# schematic.net
KiCad netlist of a schematic drawn in EasyEDA
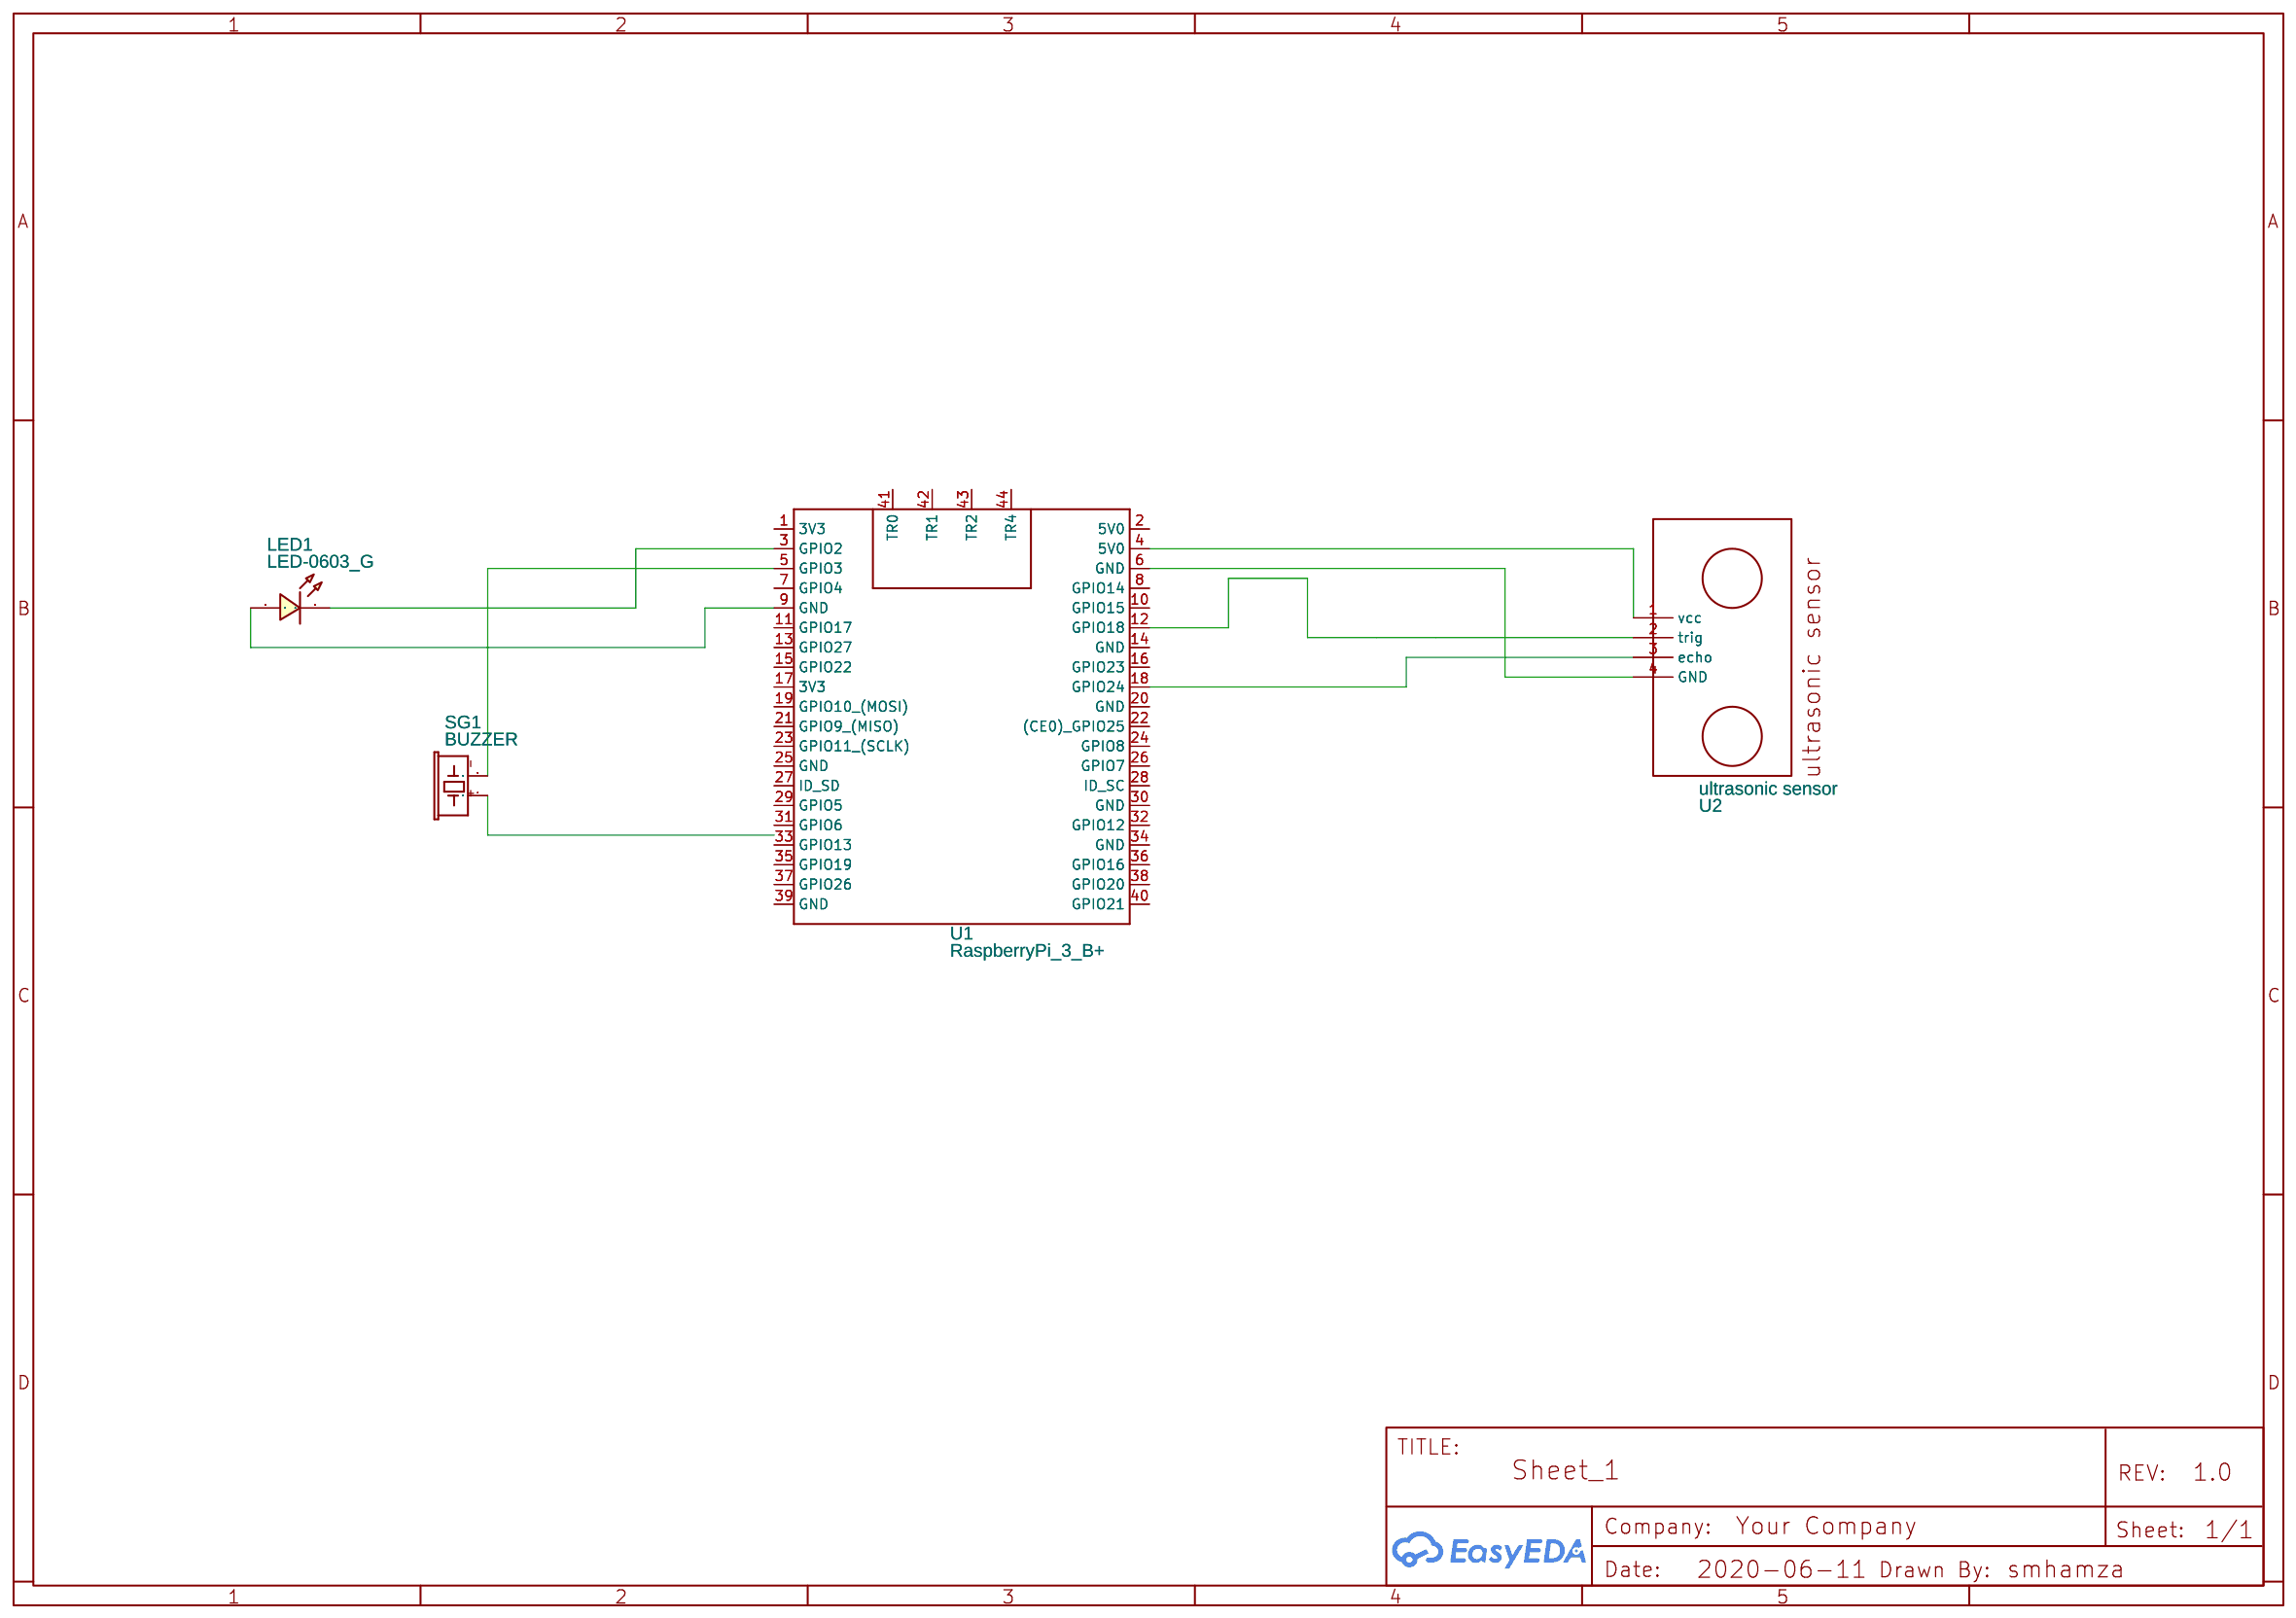
[diagram p0: schematic sheet]

(export (version "E")
  (design (tool "Eeschema 10.0.6"))
  (components
    (comp (ref "LED1")
      (value "LED-0603_G")
      (fields
        (field (name "BOM_Manufacturer Part") "19-217/GHC-YR1S2/3T")
        (field (name "BOM_Supplier Part") "C72043")
      )
      (libsource (lib "") (part "LED-0603_G"))
    )
    (comp (ref "SG1") (value "BUZZER") (libsource (lib "") (part "BUZZER")))
    (comp (ref "U1")
      (value "RaspberryPi_3_B+")
      (fields (field (name "BOM_Manufacturer Part") "RaspberryPi 3"))
      (libsource (lib "") (part "RaspberryPi_3_B+"))
    )
    (comp (ref "U2") (value "ultrasonic sensor") (libsource (lib "") (part "ultrasonic sensor")))
  )
  (nets
    (net (code "1") (name "Net-(LED1-Pad1)") (class "Default")
      (node (ref "LED1") (pin "1") (pinfunction "1_1") (pintype "unspecified"))
      (node (ref "U1") (pin "9") (pinfunction "GND_9") (pintype "unspecified"))
    )
    (net (code "2") (name "Net-(U1-GPIO2)") (class "Default")
      (node (ref "LED1") (pin "2") (pinfunction "2_2") (pintype "unspecified"))
      (node (ref "U1") (pin "3") (pinfunction "GPIO2_3") (pintype "unspecified"))
    )
    (net (code "3") (name "Net-(U1-GPIO3)") (class "Default")
      (node (ref "SG1") (pin "2") (pinfunction "2_2") (pintype "unspecified"))
      (node (ref "U1") (pin "5") (pinfunction "GPIO3_5") (pintype "unspecified"))
    )
    (net (code "4") (name "Net-(U1-GPIO18)") (class "Default")
      (node (ref "U1") (pin "12") (pinfunction "GPIO18_12") (pintype "unspecified"))
      (node (ref "U2") (pin "2") (pinfunction "trig_2") (pintype "unspecified"))
    )
    (net (code "5") (name "Net-(U1-GPIO24)") (class "Default")
      (node (ref "U1") (pin "18") (pinfunction "GPIO24_18") (pintype "unspecified"))
      (node (ref "U2") (pin "3") (pinfunction "echo_3") (pintype "unspecified"))
    )
    (net (code "6") (name "Net-(U2-GND)") (class "Default")
      (node (ref "U1") (pin "6") (pinfunction "GND_6") (pintype "unspecified"))
      (node (ref "U2") (pin "4") (pinfunction "GND_4") (pintype "unspecified"))
    )
    (net (code "7") (name "Net-(U2-vcc)") (class "Default")
      (node (ref "U1") (pin "4") (pinfunction "5V0_4") (pintype "unspecified"))
      (node (ref "U2") (pin "1") (pinfunction "vcc_1") (pintype "unspecified"))
    )
    (net (code "8") (name "unconnected-(SG1-Pad1)") (class "Default")
      (node (ref "SG1") (pin "1") (pinfunction "1_1") (pintype "unspecified"))
    )
    (net (code "9") (name "unconnected-(U1-(CE0)_GPIO25-Pad22)") (class "Default")
      (node (ref "U1") (pin "22") (pinfunction "(CE0)_GPIO25_22") (pintype "unspecified"))
    )
    (net (code "10") (name "unconnected-(U1-3V3-Pad1)") (class "Default")
      (node (ref "U1") (pin "1") (pinfunction "3V3_1") (pintype "unspecified"))
    )
    (net (code "11") (name "unconnected-(U1-3V3-Pad17)") (class "Default")
      (node (ref "U1") (pin "17") (pinfunction "3V3_17") (pintype "unspecified"))
    )
    (net (code "12") (name "unconnected-(U1-5V0-Pad2)") (class "Default")
      (node (ref "U1") (pin "2") (pinfunction "5V0_2") (pintype "unspecified"))
    )
    (net (code "13") (name "unconnected-(U1-GND-Pad14)") (class "Default")
      (node (ref "U1") (pin "14") (pinfunction "GND_14") (pintype "unspecified"))
    )
    (net (code "14") (name "unconnected-(U1-GND-Pad20)") (class "Default")
      (node (ref "U1") (pin "20") (pinfunction "GND_20") (pintype "unspecified"))
    )
    (net (code "15") (name "unconnected-(U1-GND-Pad25)") (class "Default")
      (node (ref "U1") (pin "25") (pinfunction "GND_25") (pintype "unspecified"))
    )
    (net (code "16") (name "unconnected-(U1-GND-Pad30)") (class "Default")
      (node (ref "U1") (pin "30") (pinfunction "GND_30") (pintype "unspecified"))
    )
    (net (code "17") (name "unconnected-(U1-GND-Pad34)") (class "Default")
      (node (ref "U1") (pin "34") (pinfunction "GND_34") (pintype "unspecified"))
    )
    (net (code "18") (name "unconnected-(U1-GND-Pad39)") (class "Default")
      (node (ref "U1") (pin "39") (pinfunction "GND_39") (pintype "unspecified"))
    )
    (net (code "19") (name "unconnected-(U1-GPIO4-Pad7)") (class "Default")
      (node (ref "U1") (pin "7") (pinfunction "GPIO4_7") (pintype "unspecified"))
    )
    (net (code "20") (name "unconnected-(U1-GPIO5-Pad29)") (class "Default")
      (node (ref "U1") (pin "29") (pinfunction "GPIO5_29") (pintype "unspecified"))
    )
    (net (code "21") (name "unconnected-(U1-GPIO6-Pad31)") (class "Default")
      (node (ref "U1") (pin "31") (pinfunction "GPIO6_31") (pintype "unspecified"))
    )
    (net (code "22") (name "unconnected-(U1-GPIO7-Pad26)") (class "Default")
      (node (ref "U1") (pin "26") (pinfunction "GPIO7_26") (pintype "unspecified"))
    )
    (net (code "23") (name "unconnected-(U1-GPIO8-Pad24)") (class "Default")
      (node (ref "U1") (pin "24") (pinfunction "GPIO8_24") (pintype "unspecified"))
    )
    (net (code "24") (name "unconnected-(U1-GPIO9_(MISO)-Pad21)") (class "Default")
      (node (ref "U1") (pin "21") (pinfunction "GPIO9_(MISO)_21") (pintype "unspecified"))
    )
    (net (code "25") (name "unconnected-(U1-GPIO10_(MOSI)-Pad19)") (class "Default")
      (node (ref "U1") (pin "19") (pinfunction "GPIO10_(MOSI)_19") (pintype "unspecified"))
    )
    (net (code "26") (name "unconnected-(U1-GPIO11_(SCLK)-Pad23)") (class "Default")
      (node (ref "U1") (pin "23") (pinfunction "GPIO11_(SCLK)_23") (pintype "unspecified"))
    )
    (net (code "27") (name "unconnected-(U1-GPIO12-Pad32)") (class "Default")
      (node (ref "U1") (pin "32") (pinfunction "GPIO12_32") (pintype "unspecified"))
    )
    (net (code "28") (name "unconnected-(U1-GPIO13-Pad33)") (class "Default")
      (node (ref "U1") (pin "33") (pinfunction "GPIO13_33") (pintype "unspecified"))
    )
    (net (code "29") (name "unconnected-(U1-GPIO14-Pad8)") (class "Default")
      (node (ref "U1") (pin "8") (pinfunction "GPIO14_8") (pintype "unspecified"))
    )
    (net (code "30") (name "unconnected-(U1-GPIO15-Pad10)") (class "Default")
      (node (ref "U1") (pin "10") (pinfunction "GPIO15_10") (pintype "unspecified"))
    )
    (net (code "31") (name "unconnected-(U1-GPIO16-Pad36)") (class "Default")
      (node (ref "U1") (pin "36") (pinfunction "GPIO16_36") (pintype "unspecified"))
    )
    (net (code "32") (name "unconnected-(U1-GPIO17-Pad11)") (class "Default")
      (node (ref "U1") (pin "11") (pinfunction "GPIO17_11") (pintype "unspecified"))
    )
    (net (code "33") (name "unconnected-(U1-GPIO19-Pad35)") (class "Default")
      (node (ref "U1") (pin "35") (pinfunction "GPIO19_35") (pintype "unspecified"))
    )
    (net (code "34") (name "unconnected-(U1-GPIO20-Pad38)") (class "Default")
      (node (ref "U1") (pin "38") (pinfunction "GPIO20_38") (pintype "unspecified"))
    )
    (net (code "35") (name "unconnected-(U1-GPIO21-Pad40)") (class "Default")
      (node (ref "U1") (pin "40") (pinfunction "GPIO21_40") (pintype "unspecified"))
    )
    (net (code "36") (name "unconnected-(U1-GPIO22-Pad15)") (class "Default")
      (node (ref "U1") (pin "15") (pinfunction "GPIO22_15") (pintype "unspecified"))
    )
    (net (code "37") (name "unconnected-(U1-GPIO23-Pad16)") (class "Default")
      (node (ref "U1") (pin "16") (pinfunction "GPIO23_16") (pintype "unspecified"))
    )
    (net (code "38") (name "unconnected-(U1-GPIO26-Pad37)") (class "Default")
      (node (ref "U1") (pin "37") (pinfunction "GPIO26_37") (pintype "unspecified"))
    )
    (net (code "39") (name "unconnected-(U1-GPIO27-Pad13)") (class "Default")
      (node (ref "U1") (pin "13") (pinfunction "GPIO27_13") (pintype "unspecified"))
    )
    (net (code "40") (name "unconnected-(U1-ID_SC-Pad28)") (class "Default")
      (node (ref "U1") (pin "28") (pinfunction "ID_SC_28") (pintype "unspecified"))
    )
    (net (code "41") (name "unconnected-(U1-ID_SD-Pad27)") (class "Default")
      (node (ref "U1") (pin "27") (pinfunction "ID_SD_27") (pintype "unspecified"))
    )
    (net (code "42") (name "unconnected-(U1-TR0-Pad41)") (class "Default")
      (node (ref "U1") (pin "41") (pinfunction "TR0_41") (pintype "unspecified"))
    )
    (net (code "43") (name "unconnected-(U1-TR1-Pad42)") (class "Default")
      (node (ref "U1") (pin "42") (pinfunction "TR1_42") (pintype "unspecified"))
    )
    (net (code "44") (name "unconnected-(U1-TR2-Pad43)") (class "Default")
      (node (ref "U1") (pin "43") (pinfunction "TR2_43") (pintype "unspecified"))
    )
    (net (code "45") (name "unconnected-(U1-TR4-Pad44)") (class "Default")
      (node (ref "U1") (pin "44") (pinfunction "TR4_44") (pintype "unspecified"))
    )
  )
)
